# ppc_cpld.net
KiCad netlist of a schematic drawn in Altium Designer
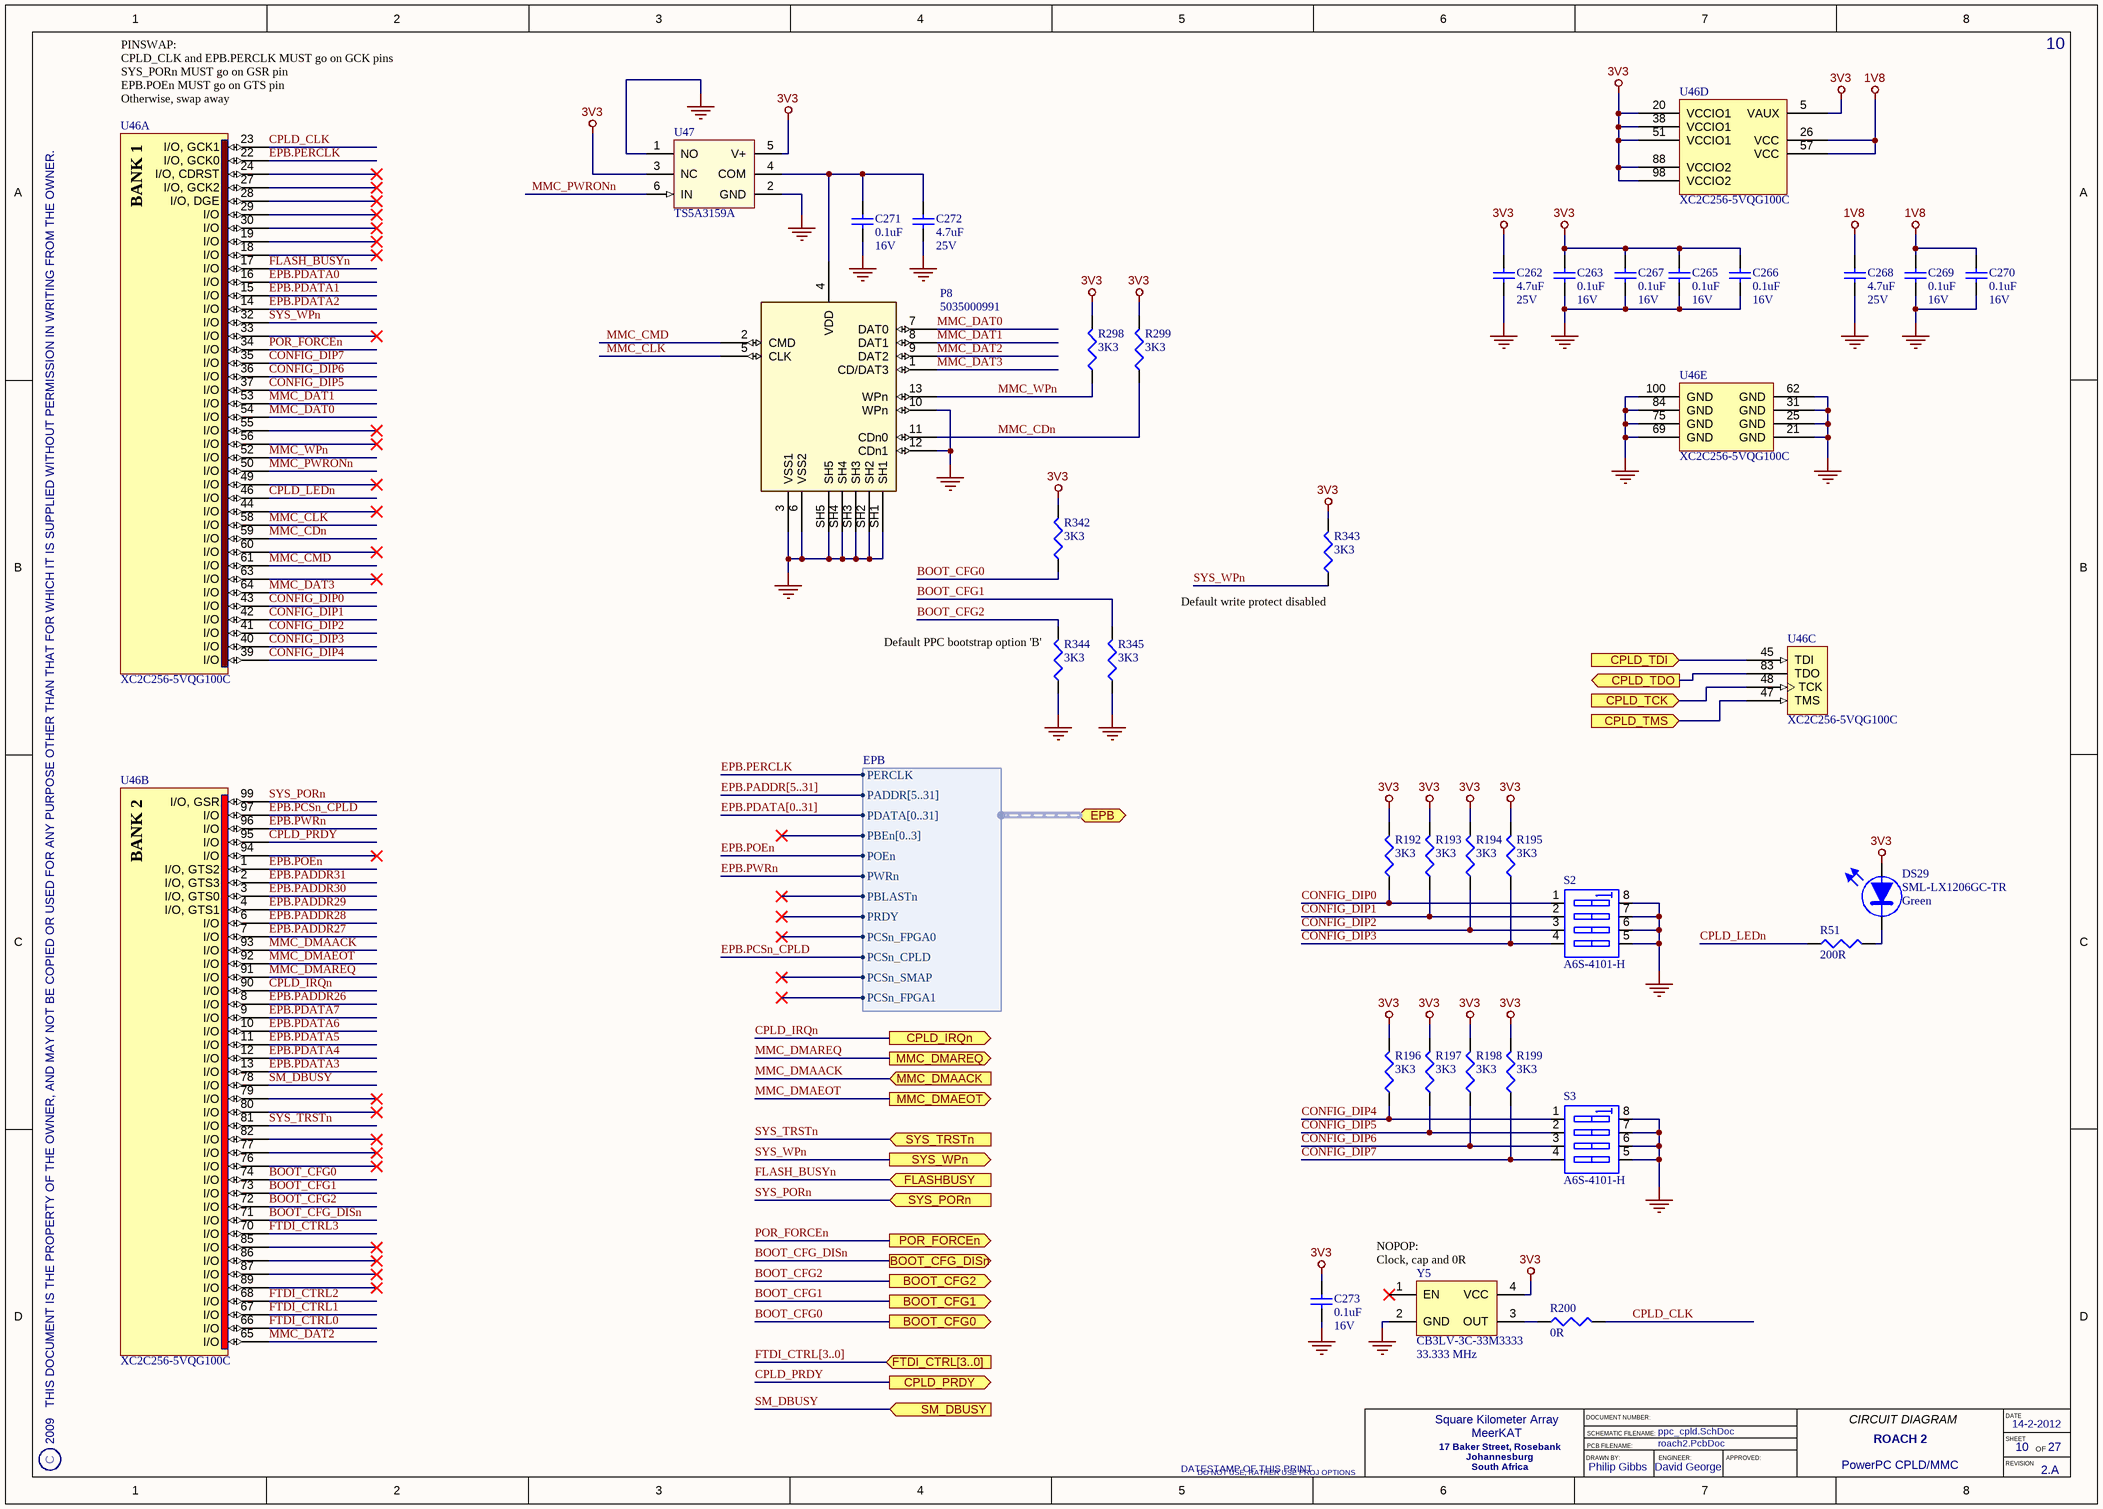
[diagram p0: ppc_cpld.SchDoc]

(export (version "E")
  (design (tool "Eeschema 10.0.6"))
  (components
    (comp (ref "C262")
      (value "4.7uF")
      (footprint "CAPC2012X127L")
      (description "4.7uF, Ceramic Capacitor")
      (fields
        (field (name "RATING") "25V")
        (field (name "MANUFACTURER") "MURATA")
        (field (name "PARTNUM") "GRM21BR61E475KA12K")
      )
      (libsource (lib "altium_db") (part "CapStd"))
    )
    (comp (ref "C263")
      (value "0.1uF")
      (footprint "CAPC1005X60L")
      (description "0.1uF, Ceramic Capacitor")
      (fields
        (field (name "RATING") "16V")
        (field (name "MANUFACTURER") "VENKEL")
        (field (name "PARTNUM") "C0402X7R160-104KN")
      )
      (libsource (lib "altium_db") (part "CapStd"))
    )
    (comp (ref "C265")
      (value "0.1uF")
      (footprint "CAPC1005X60L")
      (description "0.1uF, Ceramic Capacitor")
      (fields
        (field (name "RATING") "16V")
        (field (name "MANUFACTURER") "VENKEL")
        (field (name "PARTNUM") "C0402X7R160-104KN")
      )
      (libsource (lib "altium_db") (part "CapStd"))
    )
    (comp (ref "C266")
      (value "0.1uF")
      (footprint "CAPC1005X60L")
      (description "0.1uF, Ceramic Capacitor")
      (fields
        (field (name "RATING") "16V")
        (field (name "MANUFACTURER") "VENKEL")
        (field (name "PARTNUM") "C0402X7R160-104KN")
      )
      (libsource (lib "altium_db") (part "CapStd"))
    )
    (comp (ref "C267")
      (value "0.1uF")
      (footprint "CAPC1005X60L")
      (description "0.1uF, Ceramic Capacitor")
      (fields
        (field (name "RATING") "16V")
        (field (name "MANUFACTURER") "VENKEL")
        (field (name "PARTNUM") "C0402X7R160-104KN")
      )
      (libsource (lib "altium_db") (part "CapStd"))
    )
    (comp (ref "C268")
      (value "4.7uF")
      (footprint "CAPC2012X127L")
      (description "4.7uF, Ceramic Capacitor")
      (fields
        (field (name "RATING") "25V")
        (field (name "MANUFACTURER") "MURATA")
        (field (name "PARTNUM") "GRM21BR61E475KA12K")
      )
      (libsource (lib "altium_db") (part "CapStd"))
    )
    (comp (ref "C269")
      (value "0.1uF")
      (footprint "CAPC1005X60L")
      (description "0.1uF, Ceramic Capacitor")
      (fields
        (field (name "RATING") "16V")
        (field (name "MANUFACTURER") "VENKEL")
        (field (name "PARTNUM") "C0402X7R160-104KN")
      )
      (libsource (lib "altium_db") (part "CapStd"))
    )
    (comp (ref "C270")
      (value "0.1uF")
      (footprint "CAPC1005X60L")
      (description "0.1uF, Ceramic Capacitor")
      (fields
        (field (name "RATING") "16V")
        (field (name "MANUFACTURER") "VENKEL")
        (field (name "PARTNUM") "C0402X7R160-104KN")
      )
      (libsource (lib "altium_db") (part "CapStd"))
    )
    (comp (ref "C271")
      (value "0.1uF")
      (footprint "CAPC1005X60L")
      (description "0.1uF, Ceramic Capacitor")
      (fields
        (field (name "RATING") "16V")
        (field (name "MANUFACTURER") "VENKEL")
        (field (name "PARTNUM") "C0402X7R160-104KN")
      )
      (libsource (lib "altium_db") (part "CapStd"))
    )
    (comp (ref "C272")
      (value "4.7uF")
      (footprint "CAPC2012X127L")
      (description "4.7uF, Ceramic Capacitor")
      (fields
        (field (name "RATING") "25V")
        (field (name "MANUFACTURER") "MURATA")
        (field (name "PARTNUM") "GRM21BR61E475KA12K")
      )
      (libsource (lib "altium_db") (part "CapStd"))
    )
    (comp (ref "C273")
      (value "0.1uF")
      (footprint "CAPC1005X60L")
      (description "0.1uF, Ceramic Capacitor")
      (fields
        (field (name "RATING") "16V")
        (field (name "MANUFACTURER") "VENKEL")
        (field (name "PARTNUM") "C0402X7R160-104KN")
      )
      (libsource (lib "altium_db") (part "CapStd"))
    )
    (comp (ref "DS29")
      (value "SML-LX1206GC-TR")
      (footprint "LEDC3216X120N")
      (description "Green, Surface mount, LED, 1206")
      (fields (field (name "COLOUR") "Green") (field (name "MANUFACTURER") "LUMEX"))
      (libsource (lib "altium_db") (part "LEDSTD"))
    )
    (comp (ref "P8")
      (value "5035000991")
      (footprint "MOLEX_5035000991")
      (description "Push/Push SD Card Connector with Card Detection")
      (fields (field (name "PARTNUM") "5035000991") (field (name "MANUFACTURER") "Molex"))
      (libsource (lib "altium_db") (part "MOLEX_5035000991"))
    )
    (comp (ref "R51")
      (value "200R")
      (footprint "RESC1005X40L")
      (description "200R, 1.1mm x 0.5mm, Thick Film Resistor")
      (fields (field (name "MANUFACTURER") "ROYALOHM") (field (name "PARTNUM") "0402WGF0201T1E"))
      (libsource (lib "altium_db") (part "ResStd"))
    )
    (comp (ref "R192")
      (value "3K3")
      (footprint "RESC1005X40L")
      (description "3K3, 1.1mm x 0.5mm, Thick Film Resistor")
      (fields (field (name "MANUFACTURER") "ROYALOHM") (field (name "PARTNUM") "0402WGJ0332T1E"))
      (libsource (lib "altium_db") (part "ResStd"))
    )
    (comp (ref "R193")
      (value "3K3")
      (footprint "RESC1005X40L")
      (description "3K3, 1.1mm x 0.5mm, Thick Film Resistor")
      (fields (field (name "MANUFACTURER") "ROYALOHM") (field (name "PARTNUM") "0402WGJ0332T1E"))
      (libsource (lib "altium_db") (part "ResStd"))
    )
    (comp (ref "R194")
      (value "3K3")
      (footprint "RESC1005X40L")
      (description "3K3, 1.1mm x 0.5mm, Thick Film Resistor")
      (fields (field (name "MANUFACTURER") "ROYALOHM") (field (name "PARTNUM") "0402WGJ0332T1E"))
      (libsource (lib "altium_db") (part "ResStd"))
    )
    (comp (ref "R195")
      (value "3K3")
      (footprint "RESC1005X40L")
      (description "3K3, 1.1mm x 0.5mm, Thick Film Resistor")
      (fields (field (name "MANUFACTURER") "ROYALOHM") (field (name "PARTNUM") "0402WGJ0332T1E"))
      (libsource (lib "altium_db") (part "ResStd"))
    )
    (comp (ref "R196")
      (value "3K3")
      (footprint "RESC1005X40L")
      (description "3K3, 1.1mm x 0.5mm, Thick Film Resistor")
      (fields (field (name "MANUFACTURER") "ROYALOHM") (field (name "PARTNUM") "0402WGJ0332T1E"))
      (libsource (lib "altium_db") (part "ResStd"))
    )
    (comp (ref "R197")
      (value "3K3")
      (footprint "RESC1005X40L")
      (description "3K3, 1.1mm x 0.5mm, Thick Film Resistor")
      (fields (field (name "MANUFACTURER") "ROYALOHM") (field (name "PARTNUM") "0402WGJ0332T1E"))
      (libsource (lib "altium_db") (part "ResStd"))
    )
    (comp (ref "R198")
      (value "3K3")
      (footprint "RESC1005X40L")
      (description "3K3, 1.1mm x 0.5mm, Thick Film Resistor")
      (fields (field (name "MANUFACTURER") "ROYALOHM") (field (name "PARTNUM") "0402WGJ0332T1E"))
      (libsource (lib "altium_db") (part "ResStd"))
    )
    (comp (ref "R199")
      (value "3K3")
      (footprint "RESC1005X40L")
      (description "3K3, 1.1mm x 0.5mm, Thick Film Resistor")
      (fields (field (name "MANUFACTURER") "ROYALOHM") (field (name "PARTNUM") "0402WGJ0332T1E"))
      (libsource (lib "altium_db") (part "ResStd"))
    )
    (comp (ref "R200")
      (value "0R")
      (footprint "RESC1005X40L")
      (description "0R, 1.1mm x 0.5mm, Thick Film Resistor")
      (fields (field (name "MANUFACTURER") "ROYALOHM") (field (name "PARTNUM") "0402WG00000T1E"))
      (libsource (lib "altium_db") (part "ResStd"))
    )
    (comp (ref "R298")
      (value "3K3")
      (footprint "RESC1005X40L")
      (description "3K3, 1.1mm x 0.5mm, Thick Film Resistor")
      (fields (field (name "MANUFACTURER") "ROYALOHM") (field (name "PARTNUM") "0402WGJ0332T1E"))
      (libsource (lib "altium_db") (part "ResStd"))
    )
    (comp (ref "R299")
      (value "3K3")
      (footprint "RESC1005X40L")
      (description "3K3, 1.1mm x 0.5mm, Thick Film Resistor")
      (fields (field (name "MANUFACTURER") "ROYALOHM") (field (name "PARTNUM") "0402WGJ0332T1E"))
      (libsource (lib "altium_db") (part "ResStd"))
    )
    (comp (ref "R342")
      (value "3K3")
      (footprint "RESC1005X40L")
      (description "3K3, 1.1mm x 0.5mm, Thick Film Resistor")
      (fields (field (name "MANUFACTURER") "ROYALOHM") (field (name "PARTNUM") "0402WGJ0332T1E"))
      (libsource (lib "altium_db") (part "ResStd"))
    )
    (comp (ref "R343")
      (value "3K3")
      (footprint "RESC1005X40L")
      (description "3K3, 1.1mm x 0.5mm, Thick Film Resistor")
      (fields (field (name "MANUFACTURER") "ROYALOHM") (field (name "PARTNUM") "0402WGJ0332T1E"))
      (libsource (lib "altium_db") (part "ResStd"))
    )
    (comp (ref "R344")
      (value "3K3")
      (footprint "RESC1005X40L")
      (description "3K3, 1.1mm x 0.5mm, Thick Film Resistor")
      (fields (field (name "MANUFACTURER") "ROYALOHM") (field (name "PARTNUM") "0402WGJ0332T1E"))
      (libsource (lib "altium_db") (part "ResStd"))
    )
    (comp (ref "R345")
      (value "3K3")
      (footprint "RESC1005X40L")
      (description "3K3, 1.1mm x 0.5mm, Thick Film Resistor")
      (fields (field (name "MANUFACTURER") "ROYALOHM") (field (name "PARTNUM") "0402WGJ0332T1E"))
      (libsource (lib "altium_db") (part "ResStd"))
    )
    (comp (ref "S2")
      (value "A6S-4101-H")
      (footprint "A6S-4101-H")
      (description "4-Input, Surface mount, DIP Switch")
      (fields (field (name "PARTNUM") "A6S-4101-H") (field (name "MANUFACTURER") "OMRON"))
      (libsource (lib "altium_db") (part "A6S-4101-H"))
    )
    (comp (ref "S3")
      (value "A6S-4101-H")
      (footprint "A6S-4101-H")
      (description "4-Input, Surface mount, DIP Switch")
      (fields (field (name "PARTNUM") "A6S-4101-H") (field (name "MANUFACTURER") "OMRON"))
      (libsource (lib "altium_db") (part "A6S-4101-H"))
    )
    (comp (ref "U46")
      (value "XC2C256-5VQG100C")
      (footprint "VQG100_L")
      (description "CoolRunner-II, 1.8V, 256 Macrocell CPLD, 100-Pin VQFP, Pb-Free, Commercial Grade")
      (fields (field (name "MANUFACTURER") "Xilinx"))
      (libsource (lib "altium_db") (part "XC2C256-5VQG100C"))
    )
    (comp (ref "U47")
      (value "TS5A3159A")
      (footprint "SOT23-6")
      (description "6-pin 1 Ohm analogue switch")
      (fields (field (name "MANUFACTURER") "Texas Instruments"))
      (libsource (lib "altium_db") (part "TS5A3159A"))
    )
    (comp (ref "Y5")
      (value "CB3LV-3C-33M3333")
      (footprint "CB3X-X-XMX")
      (description "Surface mount, 33.3333 MHz, 3V3 Clock, oscillator")
      (fields
        (field (name "PARTNUM") "CB3LV-3C-33M3333")
        (field (name "FREQUENCY") "33.333 MHz")
        (field (name "MANUFACTURER") "CTS")
      )
      (libsource (lib "altium_db") (part "CB3LV-3C-33M3333"))
    )
  )
  (nets
    (net (code "48") (name "/BOOT_CFG0") (class "Default")
      (node (ref "R342") (pin "1") (pinfunction "1_1") (pintype "passive"))
      (node (ref "U46") (pin "74") (pinfunction "I/O_74") (pintype "bidirectional"))
    )
    (net (code "49") (name "/BOOT_CFG1") (class "Default")
      (node (ref "R345") (pin "2") (pinfunction "2_2") (pintype "passive"))
      (node (ref "U46") (pin "73") (pinfunction "I/O_73") (pintype "bidirectional"))
    )
    (net (code "50") (name "/BOOT_CFG2") (class "Default")
      (node (ref "R344") (pin "2") (pinfunction "2_2") (pintype "passive"))
      (node (ref "U46") (pin "72") (pinfunction "I/O_72") (pintype "bidirectional"))
    )
    (net (code "51") (name "/BOOT_CFG_DISn") (class "Default")
      (node (ref "U46") (pin "71") (pinfunction "I/O_71") (pintype "bidirectional"))
    )
    (net (code "52") (name "/CONFIG_DIP0") (class "Default")
      (node (ref "R192") (pin "1") (pinfunction "1_1") (pintype "passive"))
      (node (ref "S2") (pin "1") (pinfunction "SW1A_1") (pintype "passive"))
      (node (ref "U46") (pin "43") (pinfunction "I/O_43") (pintype "bidirectional"))
    )
    (net (code "53") (name "/CONFIG_DIP1") (class "Default")
      (node (ref "R193") (pin "1") (pinfunction "1_1") (pintype "passive"))
      (node (ref "S2") (pin "2") (pinfunction "SW2A_2") (pintype "passive"))
      (node (ref "U46") (pin "42") (pinfunction "I/O_42") (pintype "bidirectional"))
    )
    (net (code "54") (name "/CONFIG_DIP2") (class "Default")
      (node (ref "R194") (pin "1") (pinfunction "1_1") (pintype "passive"))
      (node (ref "S2") (pin "3") (pinfunction "SW3A_3") (pintype "passive"))
      (node (ref "U46") (pin "41") (pinfunction "I/O_41") (pintype "bidirectional"))
    )
    (net (code "55") (name "/CONFIG_DIP3") (class "Default")
      (node (ref "R195") (pin "1") (pinfunction "1_1") (pintype "passive"))
      (node (ref "S2") (pin "4") (pinfunction "SW4A_4") (pintype "passive"))
      (node (ref "U46") (pin "40") (pinfunction "I/O_40") (pintype "bidirectional"))
    )
    (net (code "56") (name "/CONFIG_DIP4") (class "Default")
      (node (ref "R196") (pin "1") (pinfunction "1_1") (pintype "passive"))
      (node (ref "S3") (pin "1") (pinfunction "SW1A_1") (pintype "passive"))
      (node (ref "U46") (pin "39") (pinfunction "I/O_39") (pintype "bidirectional"))
    )
    (net (code "57") (name "/CONFIG_DIP5") (class "Default")
      (node (ref "R197") (pin "1") (pinfunction "1_1") (pintype "passive"))
      (node (ref "S3") (pin "2") (pinfunction "SW2A_2") (pintype "passive"))
      (node (ref "U46") (pin "37") (pinfunction "I/O_37") (pintype "bidirectional"))
    )
    (net (code "58") (name "/CONFIG_DIP6") (class "Default")
      (node (ref "R198") (pin "1") (pinfunction "1_1") (pintype "passive"))
      (node (ref "S3") (pin "3") (pinfunction "SW3A_3") (pintype "passive"))
      (node (ref "U46") (pin "36") (pinfunction "I/O_36") (pintype "bidirectional"))
    )
    (net (code "59") (name "/CONFIG_DIP7") (class "Default")
      (node (ref "R199") (pin "1") (pinfunction "1_1") (pintype "passive"))
      (node (ref "S3") (pin "4") (pinfunction "SW4A_4") (pintype "passive"))
      (node (ref "U46") (pin "35") (pinfunction "I/O_35") (pintype "bidirectional"))
    )
    (net (code "60") (name "/CPLD_CLK") (class "Default")
      (node (ref "R200") (pin "2") (pinfunction "2_2") (pintype "passive"))
      (node (ref "U46") (pin "23") (pinfunction "I/O,_GCK1_23") (pintype "bidirectional"))
    )
    (net (code "61") (name "/CPLD_IRQn") (class "Default")
      (node (ref "U46") (pin "90") (pinfunction "I/O_90") (pintype "bidirectional"))
    )
    (net (code "62") (name "/CPLD_LEDn") (class "Default")
      (node (ref "R51") (pin "1") (pinfunction "1_1") (pintype "passive"))
      (node (ref "U46") (pin "46") (pinfunction "I/O_46") (pintype "bidirectional"))
    )
    (net (code "63") (name "/CPLD_PRDY") (class "Default")
      (node (ref "U46") (pin "95") (pinfunction "I/O_95") (pintype "bidirectional"))
    )
    (net (code "64") (name "/CPLD_TCK") (class "Default")
      (node (ref "U46") (pin "48") (pinfunction "TCK_48") (pintype "input"))
    )
    (net (code "65") (name "/CPLD_TDI") (class "Default")
      (node (ref "U46") (pin "45") (pinfunction "TDI_45") (pintype "input"))
    )
    (net (code "66") (name "/CPLD_TDO") (class "Default")
      (node (ref "U46") (pin "83") (pinfunction "TDO_83") (pintype "passive"))
    )
    (net (code "67") (name "/CPLD_TMS") (class "Default")
      (node (ref "U46") (pin "47") (pinfunction "TMS_47") (pintype "input"))
    )
    (net (code "68") (name "/EPB.PADDR26") (class "Default")
      (node (ref "U46") (pin "8") (pinfunction "I/O_8") (pintype "bidirectional"))
    )
    (net (code "69") (name "/EPB.PADDR27") (class "Default")
      (node (ref "U46") (pin "7") (pinfunction "I/O_7") (pintype "bidirectional"))
    )
    (net (code "70") (name "/EPB.PADDR28") (class "Default")
      (node (ref "U46") (pin "6") (pinfunction "I/O_6") (pintype "bidirectional"))
    )
    (net (code "71") (name "/EPB.PADDR29") (class "Default")
      (node (ref "U46") (pin "4") (pinfunction "I/O,_GTS1_4") (pintype "bidirectional"))
    )
    (net (code "72") (name "/EPB.PADDR30") (class "Default")
      (node (ref "U46") (pin "3") (pinfunction "I/O,_GTS0_3") (pintype "bidirectional"))
    )
    (net (code "73") (name "/EPB.PADDR31") (class "Default")
      (node (ref "U46") (pin "2") (pinfunction "I/O,_GTS3_2") (pintype "bidirectional"))
    )
    (net (code "75") (name "/EPB.PCSn_CPLD") (class "Default")
      (node (ref "U46") (pin "97") (pinfunction "I/O_97") (pintype "bidirectional"))
    )
    (net (code "76") (name "/EPB.PDATA0") (class "Default")
      (node (ref "U46") (pin "16") (pinfunction "I/O_16") (pintype "bidirectional"))
    )
    (net (code "77") (name "/EPB.PDATA1") (class "Default")
      (node (ref "U46") (pin "15") (pinfunction "I/O_15") (pintype "bidirectional"))
    )
    (net (code "78") (name "/EPB.PDATA2") (class "Default")
      (node (ref "U46") (pin "14") (pinfunction "I/O_14") (pintype "bidirectional"))
    )
    (net (code "79") (name "/EPB.PDATA3") (class "Default")
      (node (ref "U46") (pin "13") (pinfunction "I/O_13") (pintype "bidirectional"))
    )
    (net (code "80") (name "/EPB.PDATA4") (class "Default")
      (node (ref "U46") (pin "12") (pinfunction "I/O_12") (pintype "bidirectional"))
    )
    (net (code "81") (name "/EPB.PDATA5") (class "Default")
      (node (ref "U46") (pin "11") (pinfunction "I/O_11") (pintype "bidirectional"))
    )
    (net (code "82") (name "/EPB.PDATA6") (class "Default")
      (node (ref "U46") (pin "10") (pinfunction "I/O_10") (pintype "bidirectional"))
    )
    (net (code "83") (name "/EPB.PDATA7") (class "Default")
      (node (ref "U46") (pin "9") (pinfunction "I/O_9") (pintype "bidirectional"))
    )
    (net (code "85") (name "/EPB.PERCLK") (class "Default")
      (node (ref "U46") (pin "22") (pinfunction "I/O,_GCK0_22") (pintype "bidirectional"))
    )
    (net (code "86") (name "/EPB.POEn") (class "Default")
      (node (ref "U46") (pin "1") (pinfunction "I/O,_GTS2_1") (pintype "bidirectional"))
    )
    (net (code "87") (name "/EPB.PWRn") (class "Default")
      (node (ref "U46") (pin "96") (pinfunction "I/O_96") (pintype "bidirectional"))
    )
    (net (code "89") (name "/FLASH_BUSYn") (class "Default")
      (node (ref "U46") (pin "17") (pinfunction "I/O_17") (pintype "bidirectional"))
    )
    (net (code "90") (name "/FTDI_CTRL0") (class "Default")
      (node (ref "U46") (pin "66") (pinfunction "I/O_66") (pintype "bidirectional"))
    )
    (net (code "91") (name "/FTDI_CTRL1") (class "Default")
      (node (ref "U46") (pin "67") (pinfunction "I/O_67") (pintype "bidirectional"))
    )
    (net (code "92") (name "/FTDI_CTRL2") (class "Default")
      (node (ref "U46") (pin "68") (pinfunction "I/O_68") (pintype "bidirectional"))
    )
    (net (code "93") (name "/FTDI_CTRL3") (class "Default")
      (node (ref "U46") (pin "70") (pinfunction "I/O_70") (pintype "bidirectional"))
    )
    (net (code "95") (name "/MMC_CDn") (class "Default")
      (node (ref "P8") (pin "11") (pinfunction "CDn0_11") (pintype "bidirectional"))
      (node (ref "R299") (pin "1") (pinfunction "1_1") (pintype "passive"))
      (node (ref "U46") (pin "59") (pinfunction "I/O_59") (pintype "bidirectional"))
    )
    (net (code "96") (name "/MMC_CLK") (class "Default")
      (node (ref "P8") (pin "5") (pinfunction "CLK_5") (pintype "bidirectional"))
      (node (ref "U46") (pin "58") (pinfunction "I/O_58") (pintype "bidirectional"))
    )
    (net (code "97") (name "/MMC_CMD") (class "Default")
      (node (ref "P8") (pin "2") (pinfunction "CMD_2") (pintype "bidirectional"))
      (node (ref "U46") (pin "61") (pinfunction "I/O_61") (pintype "bidirectional"))
    )
    (net (code "98") (name "/MMC_DAT0") (class "Default")
      (node (ref "P8") (pin "7") (pinfunction "DAT0_7") (pintype "bidirectional"))
      (node (ref "U46") (pin "54") (pinfunction "I/O_54") (pintype "bidirectional"))
    )
    (net (code "99") (name "/MMC_DAT1") (class "Default")
      (node (ref "P8") (pin "8") (pinfunction "DAT1_8") (pintype "bidirectional"))
      (node (ref "U46") (pin "53") (pinfunction "I/O_53") (pintype "bidirectional"))
    )
    (net (code "100") (name "/MMC_DAT2") (class "Default")
      (node (ref "P8") (pin "9") (pinfunction "DAT2_9") (pintype "bidirectional"))
      (node (ref "U46") (pin "65") (pinfunction "I/O_65") (pintype "bidirectional"))
    )
    (net (code "101") (name "/MMC_DAT3") (class "Default")
      (node (ref "P8") (pin "1") (pinfunction "CD/DAT3_1") (pintype "bidirectional"))
      (node (ref "U46") (pin "64") (pinfunction "I/O_64") (pintype "bidirectional"))
    )
    (net (code "102") (name "/MMC_DMAACK") (class "Default")
      (node (ref "U46") (pin "93") (pinfunction "I/O_93") (pintype "bidirectional"))
    )
    (net (code "103") (name "/MMC_DMAEOT") (class "Default")
      (node (ref "U46") (pin "92") (pinfunction "I/O_92") (pintype "bidirectional"))
    )
    (net (code "104") (name "/MMC_DMAREQ") (class "Default")
      (node (ref "U46") (pin "91") (pinfunction "I/O_91") (pintype "bidirectional"))
    )
    (net (code "105") (name "/MMC_PWRONn") (class "Default")
      (node (ref "U46") (pin "50") (pinfunction "I/O_50") (pintype "bidirectional"))
      (node (ref "U47") (pin "6") (pinfunction "IN_6") (pintype "input"))
    )
    (net (code "106") (name "/MMC_WPn") (class "Default")
      (node (ref "P8") (pin "13") (pinfunction "WPn_13") (pintype "bidirectional"))
      (node (ref "R298") (pin "1") (pinfunction "1_1") (pintype "passive"))
      (node (ref "U46") (pin "52") (pinfunction "I/O_52") (pintype "bidirectional"))
    )
    (net (code "107") (name "/POR_FORCEn") (class "Default")
      (node (ref "U46") (pin "34") (pinfunction "I/O_34") (pintype "bidirectional"))
    )
    (net (code "108") (name "/SM_DBUSY") (class "Default")
      (node (ref "U46") (pin "78") (pinfunction "I/O_78") (pintype "bidirectional"))
    )
    (net (code "109") (name "/SYS_PORn") (class "Default")
      (node (ref "U46") (pin "99") (pinfunction "I/O,_GSR_99") (pintype "bidirectional"))
    )
    (net (code "110") (name "/SYS_TRSTn") (class "Default")
      (node (ref "U46") (pin "81") (pinfunction "I/O_81") (pintype "bidirectional"))
    )
    (net (code "111") (name "/SYS_WPn") (class "Default")
      (node (ref "R343") (pin "1") (pinfunction "1_1") (pintype "passive"))
      (node (ref "U46") (pin "32") (pinfunction "I/O_32") (pintype "bidirectional"))
    )
    (net (code "113") (name "1V8") (class "Default")
      (node (ref "C268") (pin "2") (pinfunction "2_2") (pintype "passive"))
      (node (ref "C269") (pin "2") (pinfunction "2_2") (pintype "passive"))
      (node (ref "C270") (pin "2") (pinfunction "2_2") (pintype "passive"))
      (node (ref "U46") (pin "26") (pinfunction "VCC_26") (pintype "power_in"))
      (node (ref "U46") (pin "57") (pinfunction "VCC_57") (pintype "power_in"))
    )
    (net (code "114") (name "3V3") (class "Default")
      (node (ref "C262") (pin "2") (pinfunction "2_2") (pintype "passive"))
      (node (ref "C263") (pin "2") (pinfunction "2_2") (pintype "passive"))
      (node (ref "C265") (pin "2") (pinfunction "2_2") (pintype "passive"))
      (node (ref "C266") (pin "2") (pinfunction "2_2") (pintype "passive"))
      (node (ref "C267") (pin "2") (pinfunction "2_2") (pintype "passive"))
      (node (ref "C273") (pin "2") (pinfunction "2_2") (pintype "passive"))
      (node (ref "DS29") (pin "2") (pinfunction "A_2") (pintype "passive"))
      (node (ref "R192") (pin "2") (pinfunction "2_2") (pintype "passive"))
      (node (ref "R193") (pin "2") (pinfunction "2_2") (pintype "passive"))
      (node (ref "R194") (pin "2") (pinfunction "2_2") (pintype "passive"))
      (node (ref "R195") (pin "2") (pinfunction "2_2") (pintype "passive"))
      (node (ref "R196") (pin "2") (pinfunction "2_2") (pintype "passive"))
      (node (ref "R197") (pin "2") (pinfunction "2_2") (pintype "passive"))
      (node (ref "R198") (pin "2") (pinfunction "2_2") (pintype "passive"))
      (node (ref "R199") (pin "2") (pinfunction "2_2") (pintype "passive"))
      (node (ref "R298") (pin "2") (pinfunction "2_2") (pintype "passive"))
      (node (ref "R299") (pin "2") (pinfunction "2_2") (pintype "passive"))
      (node (ref "R342") (pin "2") (pinfunction "2_2") (pintype "passive"))
      (node (ref "R343") (pin "2") (pinfunction "2_2") (pintype "passive"))
      (node (ref "U46") (pin "20") (pinfunction "VCCIO1_20") (pintype "power_in"))
      (node (ref "U46") (pin "38") (pinfunction "VCCIO1_38") (pintype "power_in"))
      (node (ref "U46") (pin "5") (pinfunction "VAUX_5") (pintype "power_in"))
      (node (ref "U46") (pin "51") (pinfunction "VCCIO1_51") (pintype "power_in"))
      (node (ref "U46") (pin "88") (pinfunction "VCCIO2_88") (pintype "power_in"))
      (node (ref "U46") (pin "98") (pinfunction "VCCIO2_98") (pintype "power_in"))
      (node (ref "U47") (pin "3") (pinfunction "NC_3") (pintype "passive"))
      (node (ref "U47") (pin "5") (pinfunction "V+_5") (pintype "passive"))
      (node (ref "Y5") (pin "4") (pinfunction "VCC_4") (pintype "passive"))
    )
    (net (code "115") (name "GND") (class "Default")
      (node (ref "C262") (pin "1") (pinfunction "1_1") (pintype "passive"))
      (node (ref "C263") (pin "1") (pinfunction "1_1") (pintype "passive"))
      (node (ref "C265") (pin "1") (pinfunction "1_1") (pintype "passive"))
      (node (ref "C266") (pin "1") (pinfunction "1_1") (pintype "passive"))
      (node (ref "C267") (pin "1") (pinfunction "1_1") (pintype "passive"))
      (node (ref "C268") (pin "1") (pinfunction "1_1") (pintype "passive"))
      (node (ref "C269") (pin "1") (pinfunction "1_1") (pintype "passive"))
      (node (ref "C270") (pin "1") (pinfunction "1_1") (pintype "passive"))
      (node (ref "C271") (pin "1") (pinfunction "1_1") (pintype "passive"))
      (node (ref "C272") (pin "1") (pinfunction "1_1") (pintype "passive"))
      (node (ref "C273") (pin "1") (pinfunction "1_1") (pintype "passive"))
      (node (ref "P8") (pin "10") (pinfunction "WPn_10") (pintype "bidirectional"))
      (node (ref "P8") (pin "12") (pinfunction "CDn1_12") (pintype "bidirectional"))
      (node (ref "P8") (pin "3") (pinfunction "VSS1_3") (pintype "power_in"))
      (node (ref "P8") (pin "6") (pinfunction "VSS2_6") (pintype "power_in"))
      (node (ref "P8") (pin "SH1") (pinfunction "SH1_SH1") (pintype "power_in"))
      (node (ref "P8") (pin "SH2") (pinfunction "SH2_SH2") (pintype "power_in"))
      (node (ref "P8") (pin "SH3") (pinfunction "SH3_SH3") (pintype "power_in"))
      (node (ref "P8") (pin "SH4") (pinfunction "SH4_SH4") (pintype "power_in"))
      (node (ref "P8") (pin "SH5") (pinfunction "SH5_SH5") (pintype "power_in"))
      (node (ref "R344") (pin "1") (pinfunction "1_1") (pintype "passive"))
      (node (ref "R345") (pin "1") (pinfunction "1_1") (pintype "passive"))
      (node (ref "S2") (pin "5") (pinfunction "SW4B_5") (pintype "passive"))
      (node (ref "S2") (pin "6") (pinfunction "SW3B_6") (pintype "passive"))
      (node (ref "S2") (pin "7") (pinfunction "SW2B_7") (pintype "passive"))
      (node (ref "S2") (pin "8") (pinfunction "SW1B_8") (pintype "passive"))
      (node (ref "S3") (pin "5") (pinfunction "SW4B_5") (pintype "passive"))
      (node (ref "S3") (pin "6") (pinfunction "SW3B_6") (pintype "passive"))
      (node (ref "S3") (pin "7") (pinfunction "SW2B_7") (pintype "passive"))
      (node (ref "S3") (pin "8") (pinfunction "SW1B_8") (pintype "passive"))
      (node (ref "U46") (pin "100") (pinfunction "GND_100") (pintype "power_in"))
      (node (ref "U46") (pin "21") (pinfunction "GND_21") (pintype "power_in"))
      (node (ref "U46") (pin "25") (pinfunction "GND_25") (pintype "power_in"))
      (node (ref "U46") (pin "31") (pinfunction "GND_31") (pintype "power_in"))
      (node (ref "U46") (pin "62") (pinfunction "GND_62") (pintype "power_in"))
      (node (ref "U46") (pin "69") (pinfunction "GND_69") (pintype "power_in"))
      (node (ref "U46") (pin "75") (pinfunction "GND_75") (pintype "power_in"))
      (node (ref "U46") (pin "84") (pinfunction "GND_84") (pintype "power_in"))
      (node (ref "U47") (pin "1") (pinfunction "NO_1") (pintype "passive"))
      (node (ref "U47") (pin "2") (pinfunction "GND_2") (pintype "passive"))
      (node (ref "Y5") (pin "2") (pinfunction "GND_2") (pintype "passive"))
    )
    (net (code "116") (name "Net-(DS29-K)") (class "Default")
      (node (ref "DS29") (pin "1") (pinfunction "K_1") (pintype "passive"))
      (node (ref "R51") (pin "2") (pinfunction "2_2") (pintype "passive"))
    )
    (net (code "117") (name "Net-(P8-VDD)") (class "Default")
      (node (ref "C271") (pin "2") (pinfunction "2_2") (pintype "passive"))
      (node (ref "C272") (pin "2") (pinfunction "2_2") (pintype "passive"))
      (node (ref "P8") (pin "4") (pinfunction "VDD_4") (pintype "power_in"))
      (node (ref "U47") (pin "4") (pinfunction "COM_4") (pintype "passive"))
    )
    (net (code "118") (name "Net-(Y5-OUT)") (class "Default")
      (node (ref "R200") (pin "1") (pinfunction "1_1") (pintype "passive"))
      (node (ref "Y5") (pin "3") (pinfunction "OUT_3") (pintype "passive"))
    )
    (net (code "119") (name "unconnected-(U46A-I{slash}O,_CDRST-Pad24)") (class "Default")
      (node (ref "U46") (pin "24") (pinfunction "I/O,_CDRST_24") (pintype "bidirectional+no_connect"))
    )
    (net (code "120") (name "unconnected-(U46A-I{slash}O,_DGE-Pad28)") (class "Default")
      (node (ref "U46") (pin "28") (pinfunction "I/O,_DGE_28") (pintype "bidirectional+no_connect"))
    )
    (net (code "121") (name "unconnected-(U46A-I{slash}O,_GCK2-Pad27)") (class "Default")
      (node (ref "U46") (pin "27") (pinfunction "I/O,_GCK2_27") (pintype "bidirectional+no_connect"))
    )
    (net (code "122") (name "unconnected-(U46A-I{slash}O-Pad18)") (class "Default")
      (node (ref "U46") (pin "18") (pinfunction "I/O_18") (pintype "bidirectional+no_connect"))
    )
    (net (code "123") (name "unconnected-(U46A-I{slash}O-Pad19)") (class "Default")
      (node (ref "U46") (pin "19") (pinfunction "I/O_19") (pintype "bidirectional+no_connect"))
    )
    (net (code "124") (name "unconnected-(U46A-I{slash}O-Pad29)") (class "Default")
      (node (ref "U46") (pin "29") (pinfunction "I/O_29") (pintype "bidirectional+no_connect"))
    )
    (net (code "125") (name "unconnected-(U46A-I{slash}O-Pad30)") (class "Default")
      (node (ref "U46") (pin "30") (pinfunction "I/O_30") (pintype "bidirectional+no_connect"))
    )
    (net (code "126") (name "unconnected-(U46A-I{slash}O-Pad33)") (class "Default")
      (node (ref "U46") (pin "33") (pinfunction "I/O_33") (pintype "bidirectional+no_connect"))
    )
    (net (code "127") (name "unconnected-(U46A-I{slash}O-Pad44)") (class "Default")
      (node (ref "U46") (pin "44") (pinfunction "I/O_44") (pintype "bidirectional+no_connect"))
    )
    (net (code "128") (name "unconnected-(U46A-I{slash}O-Pad49)") (class "Default")
      (node (ref "U46") (pin "49") (pinfunction "I/O_49") (pintype "bidirectional+no_connect"))
    )
    (net (code "129") (name "unconnected-(U46A-I{slash}O-Pad55)") (class "Default")
      (node (ref "U46") (pin "55") (pinfunction "I/O_55") (pintype "bidirectional+no_connect"))
    )
    (net (code "130") (name "unconnected-(U46A-I{slash}O-Pad56)") (class "Default")
      (node (ref "U46") (pin "56") (pinfunction "I/O_56") (pintype "bidirectional+no_connect"))
    )
    (net (code "131") (name "unconnected-(U46A-I{slash}O-Pad60)") (class "Default")
      (node (ref "U46") (pin "60") (pinfunction "I/O_60") (pintype "bidirectional+no_connect"))
    )
    (net (code "132") (name "unconnected-(U46A-I{slash}O-Pad63)") (class "Default")
      (node (ref "U46") (pin "63") (pinfunction "I/O_63") (pintype "bidirectional+no_connect"))
    )
    (net (code "133") (name "unconnected-(U46B-I{slash}O-Pad76)") (class "Default")
      (node (ref "U46") (pin "76") (pinfunction "I/O_76") (pintype "bidirectional+no_connect"))
    )
    (net (code "134") (name "unconnected-(U46B-I{slash}O-Pad77)") (class "Default")
      (node (ref "U46") (pin "77") (pinfunction "I/O_77") (pintype "bidirectional+no_connect"))
    )
    (net (code "135") (name "unconnected-(U46B-I{slash}O-Pad79)") (class "Default")
      (node (ref "U46") (pin "79") (pinfunction "I/O_79") (pintype "bidirectional+no_connect"))
    )
    (net (code "136") (name "unconnected-(U46B-I{slash}O-Pad80)") (class "Default")
      (node (ref "U46") (pin "80") (pinfunction "I/O_80") (pintype "bidirectional+no_connect"))
    )
    (net (code "137") (name "unconnected-(U46B-I{slash}O-Pad82)") (class "Default")
      (node (ref "U46") (pin "82") (pinfunction "I/O_82") (pintype "bidirectional+no_connect"))
    )
    (net (code "138") (name "unconnected-(U46B-I{slash}O-Pad85)") (class "Default")
      (node (ref "U46") (pin "85") (pinfunction "I/O_85") (pintype "bidirectional+no_connect"))
    )
    (net (code "139") (name "unconnected-(U46B-I{slash}O-Pad86)") (class "Default")
      (node (ref "U46") (pin "86") (pinfunction "I/O_86") (pintype "bidirectional+no_connect"))
    )
    (net (code "140") (name "unconnected-(U46B-I{slash}O-Pad87)") (class "Default")
      (node (ref "U46") (pin "87") (pinfunction "I/O_87") (pintype "bidirectional+no_connect"))
    )
    (net (code "141") (name "unconnected-(U46B-I{slash}O-Pad89)") (class "Default")
      (node (ref "U46") (pin "89") (pinfunction "I/O_89") (pintype "bidirectional+no_connect"))
    )
    (net (code "142") (name "unconnected-(U46B-I{slash}O-Pad94)") (class "Default")
      (node (ref "U46") (pin "94") (pinfunction "I/O_94") (pintype "bidirectional+no_connect"))
    )
    (net (code "143") (name "unconnected-(Y5-EN-Pad1)") (class "Default")
      (node (ref "Y5") (pin "1") (pinfunction "EN_1") (pintype "passive+no_connect"))
    )
  )
)
